# cubex_solar.net
KiCad netlist of a schematic drawn in EAGLE
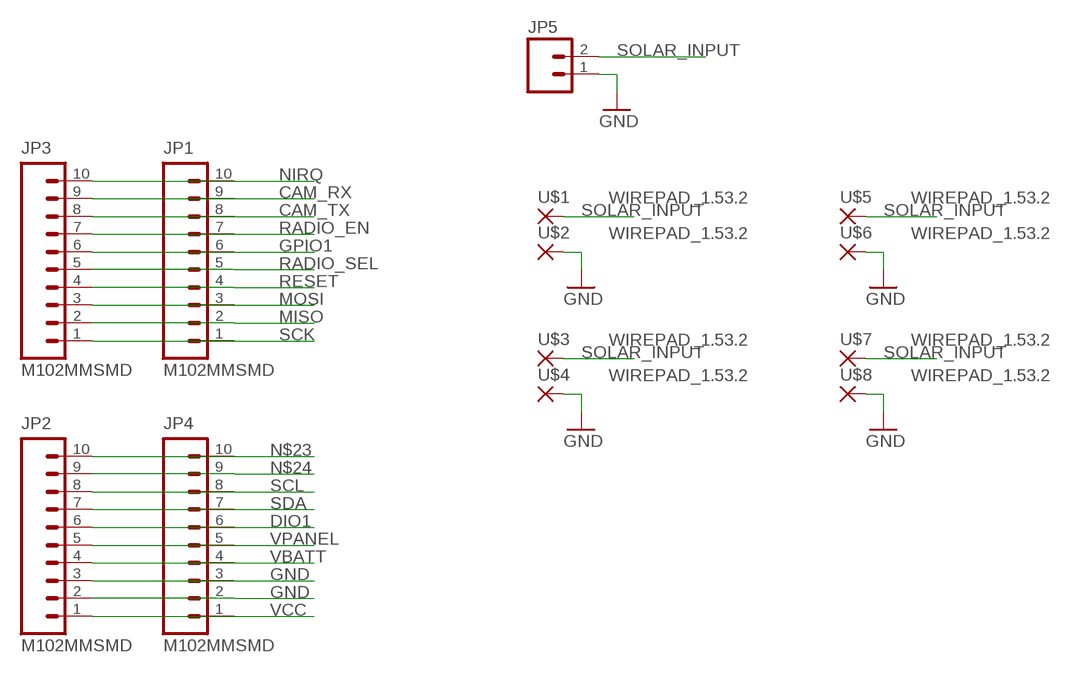
[diagram p0: schematic, sheet 1]

(export (version "E")
  (design (tool "Eeschema 10.0.6"))
  (components
    (comp (ref "JP1")
      (value "M102MMSMD")
      (footprint "eagle-import:1X10-2MM-SMD")
      (libsource (lib "eagle-import") (part "M102MMSMD"))
    )
    (comp (ref "JP2")
      (value "M102MMSMD")
      (footprint "eagle-import:1X10-2MM-SMD")
      (libsource (lib "eagle-import") (part "M102MMSMD"))
    )
    (comp (ref "JP3")
      (value "M102MMSMD")
      (footprint "eagle-import:1X10-2MM-SMD")
      (libsource (lib "eagle-import") (part "M102MMSMD"))
    )
    (comp (ref "JP4")
      (value "M102MMSMD")
      (footprint "eagle-import:1X10-2MM-SMD")
      (libsource (lib "eagle-import") (part "M102MMSMD"))
    )
    (comp (ref "JP5")
      (value "M02JST-PTH-2")
      (footprint "eagle-import:JST-2-PTH")
      (libsource (lib "eagle-import") (part "M02JST-PTH-2"))
    )
    (comp (ref "U$1")
      (value "WIREPAD_1.53.2")
      (footprint "eagle-import:WIREPAD_3.2X1.5MM")
      (libsource (lib "eagle-import") (part "WIREPAD_1.53.2"))
    )
    (comp (ref "U$2")
      (value "WIREPAD_1.53.2")
      (footprint "eagle-import:WIREPAD_3.2X1.5MM")
      (libsource (lib "eagle-import") (part "WIREPAD_1.53.2"))
    )
    (comp (ref "U$3")
      (value "WIREPAD_1.53.2")
      (footprint "eagle-import:WIREPAD_3.2X1.5MM")
      (libsource (lib "eagle-import") (part "WIREPAD_1.53.2"))
    )
    (comp (ref "U$4")
      (value "WIREPAD_1.53.2")
      (footprint "eagle-import:WIREPAD_3.2X1.5MM")
      (libsource (lib "eagle-import") (part "WIREPAD_1.53.2"))
    )
    (comp (ref "U$5")
      (value "WIREPAD_1.53.2")
      (footprint "eagle-import:WIREPAD_3.2X1.5MM")
      (libsource (lib "eagle-import") (part "WIREPAD_1.53.2"))
    )
    (comp (ref "U$6")
      (value "WIREPAD_1.53.2")
      (footprint "eagle-import:WIREPAD_3.2X1.5MM")
      (libsource (lib "eagle-import") (part "WIREPAD_1.53.2"))
    )
    (comp (ref "U$7")
      (value "WIREPAD_1.53.2")
      (footprint "eagle-import:WIREPAD_3.2X1.5MM")
      (libsource (lib "eagle-import") (part "WIREPAD_1.53.2"))
    )
    (comp (ref "U$8")
      (value "WIREPAD_1.53.2")
      (footprint "eagle-import:WIREPAD_3.2X1.5MM")
      (libsource (lib "eagle-import") (part "WIREPAD_1.53.2"))
    )
  )
  (nets
    (net (code "1") (name "/CAM_RX") (class "Default")
      (node (ref "JP1") (pin "9") (pinfunction "9_9") (pintype "passive"))
      (node (ref "JP3") (pin "9") (pinfunction "9_9") (pintype "passive"))
    )
    (net (code "2") (name "/CAM_TX") (class "Default")
      (node (ref "JP1") (pin "8") (pinfunction "8_8") (pintype "passive"))
      (node (ref "JP3") (pin "8") (pinfunction "8_8") (pintype "passive"))
    )
    (net (code "3") (name "/DIO1") (class "Default")
      (node (ref "JP2") (pin "6") (pinfunction "6_6") (pintype "passive"))
      (node (ref "JP4") (pin "6") (pinfunction "6_6") (pintype "passive"))
    )
    (net (code "4") (name "/GPIO1") (class "Default")
      (node (ref "JP1") (pin "6") (pinfunction "6_6") (pintype "passive"))
      (node (ref "JP3") (pin "6") (pinfunction "6_6") (pintype "passive"))
    )
    (net (code "5") (name "/MISO") (class "Default")
      (node (ref "JP1") (pin "2") (pinfunction "2_2") (pintype "passive"))
      (node (ref "JP3") (pin "2") (pinfunction "2_2") (pintype "passive"))
    )
    (net (code "6") (name "/MOSI") (class "Default")
      (node (ref "JP1") (pin "3") (pinfunction "3_3") (pintype "passive"))
      (node (ref "JP3") (pin "3") (pinfunction "3_3") (pintype "passive"))
    )
    (net (code "7") (name "/N$23") (class "Default")
      (node (ref "JP2") (pin "10") (pinfunction "10_10") (pintype "passive"))
      (node (ref "JP4") (pin "10") (pinfunction "10_10") (pintype "passive"))
    )
    (net (code "8") (name "/N$24") (class "Default")
      (node (ref "JP2") (pin "9") (pinfunction "9_9") (pintype "passive"))
      (node (ref "JP4") (pin "9") (pinfunction "9_9") (pintype "passive"))
    )
    (net (code "9") (name "/NIRQ") (class "Default")
      (node (ref "JP1") (pin "10") (pinfunction "10_10") (pintype "passive"))
      (node (ref "JP3") (pin "10") (pinfunction "10_10") (pintype "passive"))
    )
    (net (code "10") (name "/RADIO_EN") (class "Default")
      (node (ref "JP1") (pin "7") (pinfunction "7_7") (pintype "passive"))
      (node (ref "JP3") (pin "7") (pinfunction "7_7") (pintype "passive"))
    )
    (net (code "11") (name "/RADIO_SEL") (class "Default")
      (node (ref "JP1") (pin "5") (pinfunction "5_5") (pintype "passive"))
      (node (ref "JP3") (pin "5") (pinfunction "5_5") (pintype "passive"))
    )
    (net (code "12") (name "/RESET") (class "Default")
      (node (ref "JP1") (pin "4") (pinfunction "4_4") (pintype "passive"))
      (node (ref "JP3") (pin "4") (pinfunction "4_4") (pintype "passive"))
    )
    (net (code "13") (name "/SCK") (class "Default")
      (node (ref "JP1") (pin "1") (pinfunction "1_1") (pintype "passive"))
      (node (ref "JP3") (pin "1") (pinfunction "1_1") (pintype "passive"))
    )
    (net (code "14") (name "/SCL") (class "Default")
      (node (ref "JP2") (pin "8") (pinfunction "8_8") (pintype "passive"))
      (node (ref "JP4") (pin "8") (pinfunction "8_8") (pintype "passive"))
    )
    (net (code "15") (name "/SDA") (class "Default")
      (node (ref "JP2") (pin "7") (pinfunction "7_7") (pintype "passive"))
      (node (ref "JP4") (pin "7") (pinfunction "7_7") (pintype "passive"))
    )
    (net (code "16") (name "/SOLAR_INPUT") (class "Default")
      (node (ref "JP5") (pin "2") (pinfunction "2_2") (pintype "passive"))
      (node (ref "U$1") (pin "1") (pinfunction "P_1") (pintype "passive"))
      (node (ref "U$3") (pin "1") (pinfunction "P_1") (pintype "passive"))
      (node (ref "U$5") (pin "1") (pinfunction "P_1") (pintype "passive"))
      (node (ref "U$7") (pin "1") (pinfunction "P_1") (pintype "passive"))
    )
    (net (code "17") (name "/VBATT") (class "Default")
      (node (ref "JP2") (pin "4") (pinfunction "4_4") (pintype "passive"))
      (node (ref "JP4") (pin "4") (pinfunction "4_4") (pintype "passive"))
    )
    (net (code "18") (name "/VCC") (class "Default")
      (node (ref "JP2") (pin "1") (pinfunction "1_1") (pintype "passive"))
      (node (ref "JP4") (pin "1") (pinfunction "1_1") (pintype "passive"))
    )
    (net (code "19") (name "/VPANEL") (class "Default")
      (node (ref "JP2") (pin "5") (pinfunction "5_5") (pintype "passive"))
      (node (ref "JP4") (pin "5") (pinfunction "5_5") (pintype "passive"))
    )
    (net (code "20") (name "GND") (class "Default")
      (node (ref "JP2") (pin "2") (pinfunction "2_2") (pintype "passive"))
      (node (ref "JP2") (pin "3") (pinfunction "3_3") (pintype "passive"))
      (node (ref "JP4") (pin "2") (pinfunction "2_2") (pintype "passive"))
      (node (ref "JP4") (pin "3") (pinfunction "3_3") (pintype "passive"))
      (node (ref "JP5") (pin "1") (pinfunction "1_1") (pintype "passive"))
      (node (ref "U$2") (pin "1") (pinfunction "P_1") (pintype "passive"))
      (node (ref "U$4") (pin "1") (pinfunction "P_1") (pintype "passive"))
      (node (ref "U$6") (pin "1") (pinfunction "P_1") (pintype "passive"))
      (node (ref "U$8") (pin "1") (pinfunction "P_1") (pintype "passive"))
    )
  )
)
